# MPPT-BCR.net
KiCad netlist of a schematic drawn in Altium Designer
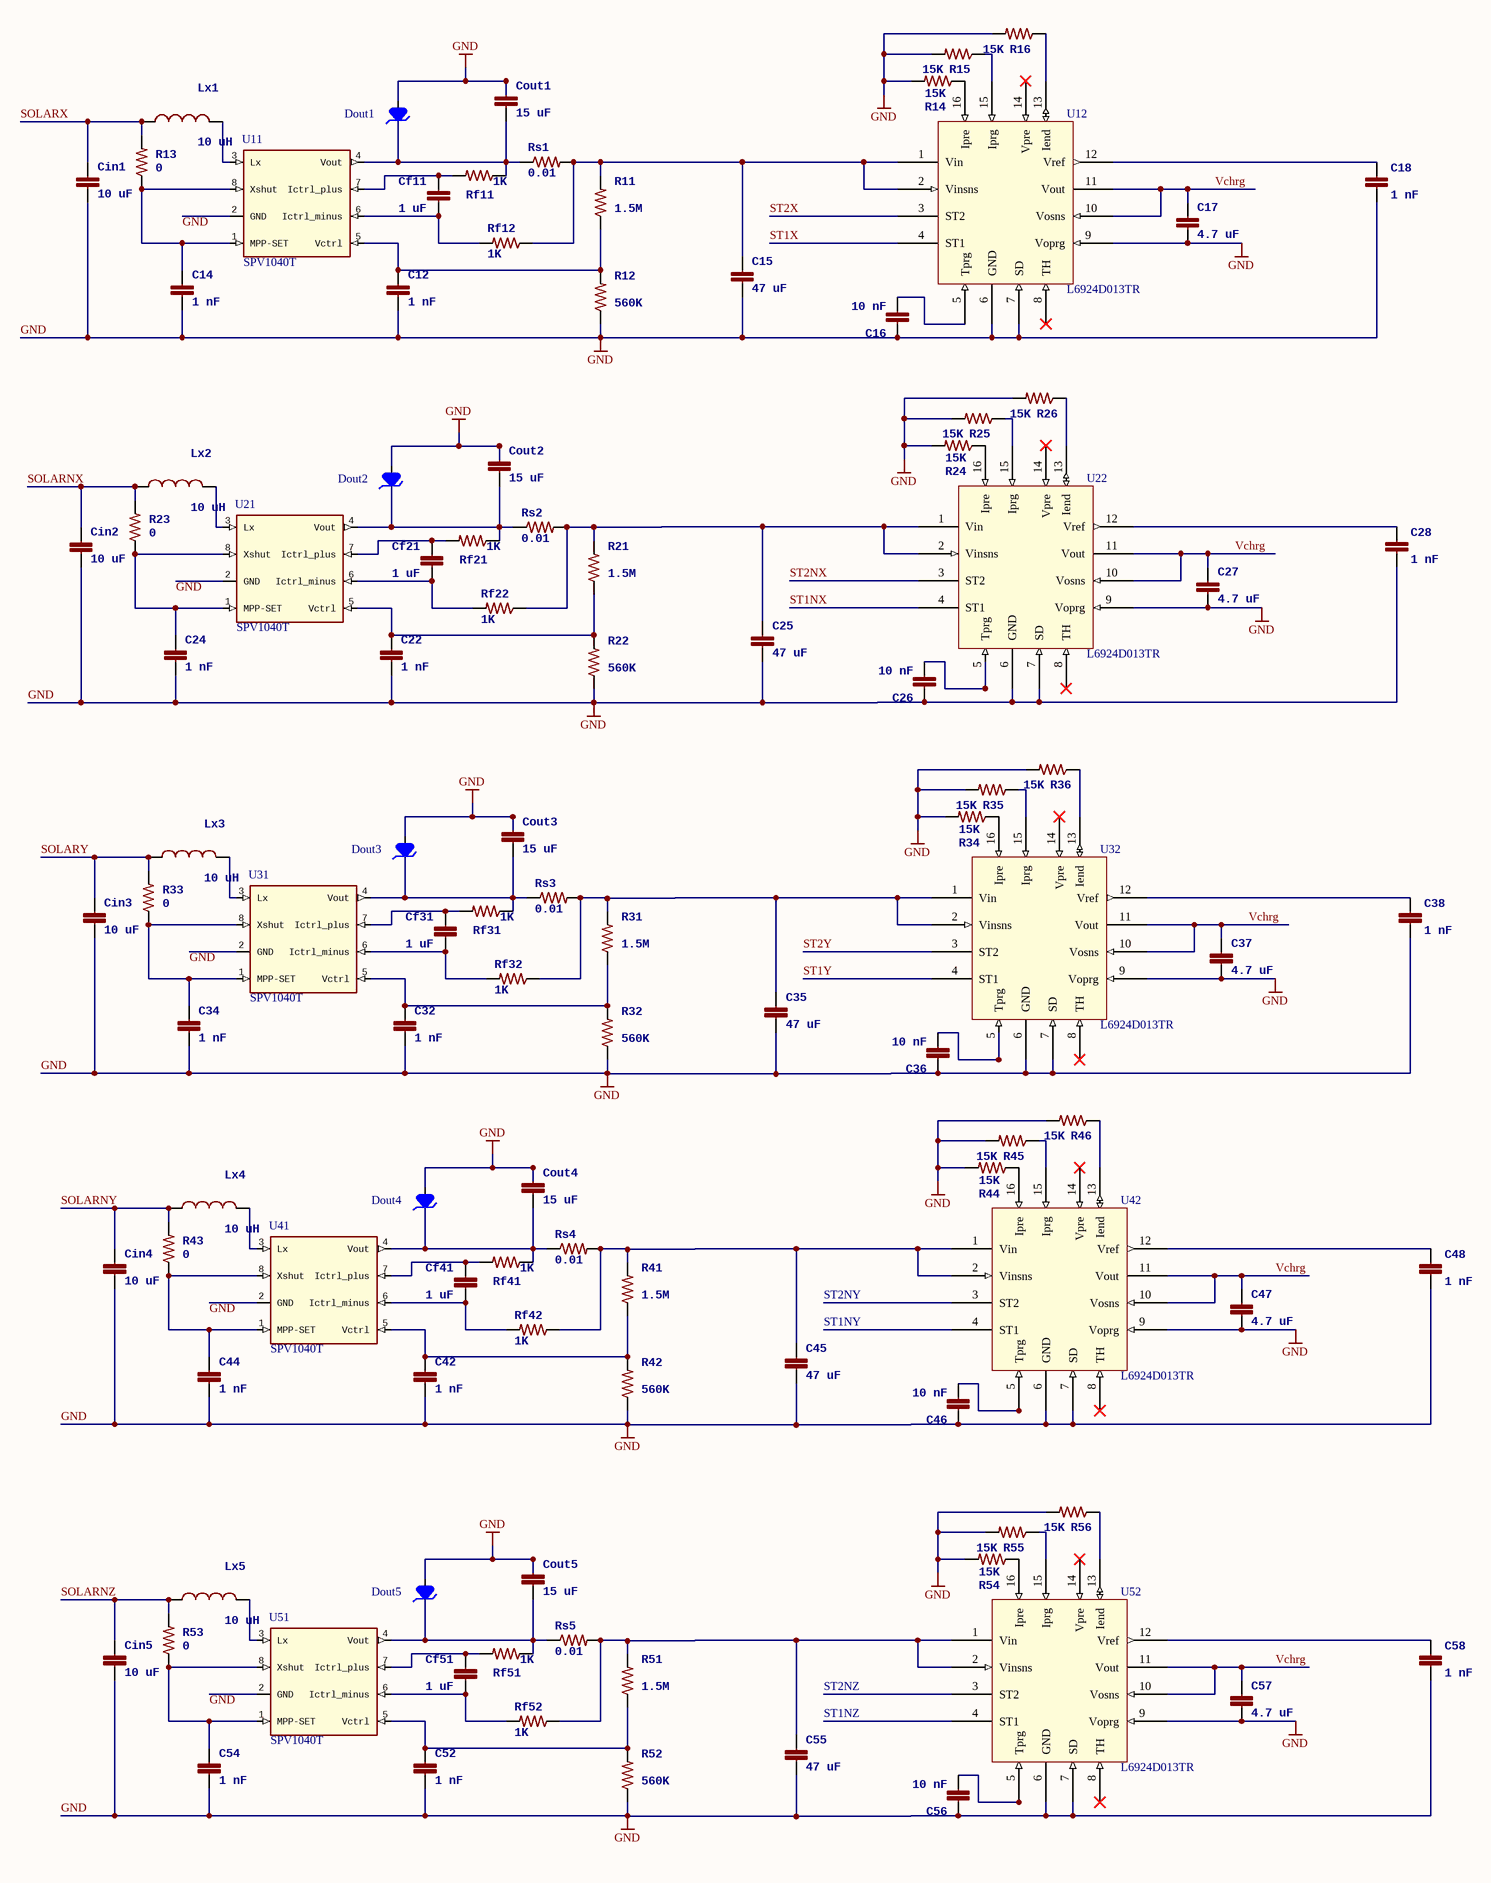
[diagram p0: MPPT-BCR.SchDoc]

(export (version "E")
  (design (tool "Eeschema 10.0.6"))
  (components
    (comp (ref "C12")
      (value "1 nF")
      (footprint "0805")
      (fields (field (name "TOLERANCE") "±10%"))
      (libsource (lib "yusend_power") (part "CAP0805_1nF"))
    )
    (comp (ref "C14")
      (value "1 nF")
      (footprint "0805")
      (fields (field (name "TOLERANCE") "±10%"))
      (libsource (lib "yusend_power") (part "CAP0805_1nF"))
    )
    (comp (ref "C15")
      (value "47 uF")
      (footprint "0805")
      (fields (field (name "TOLERANCE") "±10%"))
      (libsource (lib "yusend_power") (part "CAP0805_47000nF"))
    )
    (comp (ref "C16")
      (value "10 nF")
      (footprint "0805")
      (fields (field (name "TOLERANCE") "±10%"))
      (libsource (lib "yusend_power") (part "CAP0805_10nF"))
    )
    (comp (ref "C17")
      (value "4.7 uF")
      (footprint "0805")
      (fields (field (name "TOLERANCE") "±10%"))
      (libsource (lib "yusend_power") (part "CAP0805_4700nF"))
    )
    (comp (ref "C18")
      (value "1 nF")
      (footprint "0805")
      (fields (field (name "TOLERANCE") "±10%"))
      (libsource (lib "yusend_power") (part "CAP0805_1nF"))
    )
    (comp (ref "C22")
      (value "1 nF")
      (footprint "0805")
      (fields (field (name "TOLERANCE") "±10%"))
      (libsource (lib "yusend_power") (part "CAP0805_1nF"))
    )
    (comp (ref "C24")
      (value "1 nF")
      (footprint "0805")
      (fields (field (name "TOLERANCE") "±10%"))
      (libsource (lib "yusend_power") (part "CAP0805_1nF"))
    )
    (comp (ref "C25")
      (value "47 uF")
      (footprint "0805")
      (fields (field (name "TOLERANCE") "±10%"))
      (libsource (lib "yusend_power") (part "CAP0805_47000nF"))
    )
    (comp (ref "C26")
      (value "10 nF")
      (footprint "0805")
      (fields (field (name "TOLERANCE") "±10%"))
      (libsource (lib "yusend_power") (part "CAP0805_10nF"))
    )
    (comp (ref "C27")
      (value "4.7 uF")
      (footprint "0805")
      (fields (field (name "TOLERANCE") "±10%"))
      (libsource (lib "yusend_power") (part "CAP0805_4700nF"))
    )
    (comp (ref "C28")
      (value "1 nF")
      (footprint "0805")
      (fields (field (name "TOLERANCE") "±10%"))
      (libsource (lib "yusend_power") (part "CAP0805_1nF"))
    )
    (comp (ref "C32")
      (value "1 nF")
      (footprint "0805")
      (fields (field (name "TOLERANCE") "±10%"))
      (libsource (lib "yusend_power") (part "CAP0805_1nF"))
    )
    (comp (ref "C34")
      (value "1 nF")
      (footprint "0805")
      (fields (field (name "TOLERANCE") "±10%"))
      (libsource (lib "yusend_power") (part "CAP0805_1nF"))
    )
    (comp (ref "C35")
      (value "47 uF")
      (footprint "0805")
      (fields (field (name "TOLERANCE") "±10%"))
      (libsource (lib "yusend_power") (part "CAP0805_47000nF"))
    )
    (comp (ref "C36")
      (value "10 nF")
      (footprint "0805")
      (fields (field (name "TOLERANCE") "±10%"))
      (libsource (lib "yusend_power") (part "CAP0805_10nF"))
    )
    (comp (ref "C37")
      (value "4.7 uF")
      (footprint "0805")
      (fields (field (name "TOLERANCE") "±10%"))
      (libsource (lib "yusend_power") (part "CAP0805_4700nF"))
    )
    (comp (ref "C38")
      (value "1 nF")
      (footprint "0805")
      (fields (field (name "TOLERANCE") "±10%"))
      (libsource (lib "yusend_power") (part "CAP0805_1nF"))
    )
    (comp (ref "C42")
      (value "1 nF")
      (footprint "0805")
      (fields (field (name "TOLERANCE") "±10%"))
      (libsource (lib "yusend_power") (part "CAP0805_1nF"))
    )
    (comp (ref "C44")
      (value "1 nF")
      (footprint "0805")
      (fields (field (name "TOLERANCE") "±10%"))
      (libsource (lib "yusend_power") (part "CAP0805_1nF"))
    )
    (comp (ref "C45")
      (value "47 uF")
      (footprint "0805")
      (fields (field (name "TOLERANCE") "±10%"))
      (libsource (lib "yusend_power") (part "CAP0805_47000nF"))
    )
    (comp (ref "C46")
      (value "10 nF")
      (footprint "0805")
      (fields (field (name "TOLERANCE") "±10%"))
      (libsource (lib "yusend_power") (part "CAP0805_10nF"))
    )
    (comp (ref "C47")
      (value "4.7 uF")
      (footprint "0805")
      (fields (field (name "TOLERANCE") "±10%"))
      (libsource (lib "yusend_power") (part "CAP0805_4700nF"))
    )
    (comp (ref "C48")
      (value "1 nF")
      (footprint "0805")
      (fields (field (name "TOLERANCE") "±10%"))
      (libsource (lib "yusend_power") (part "CAP0805_1nF"))
    )
    (comp (ref "C52")
      (value "1 nF")
      (footprint "0805")
      (fields (field (name "TOLERANCE") "±10%"))
      (libsource (lib "yusend_power") (part "CAP0805_1nF"))
    )
    (comp (ref "C54")
      (value "1 nF")
      (footprint "0805")
      (fields (field (name "TOLERANCE") "±10%"))
      (libsource (lib "yusend_power") (part "CAP0805_1nF"))
    )
    (comp (ref "C55")
      (value "47 uF")
      (footprint "0805")
      (fields (field (name "TOLERANCE") "±10%"))
      (libsource (lib "yusend_power") (part "CAP0805_47000nF"))
    )
    (comp (ref "C56")
      (value "10 nF")
      (footprint "0805")
      (fields (field (name "TOLERANCE") "±10%"))
      (libsource (lib "yusend_power") (part "CAP0805_10nF"))
    )
    (comp (ref "C57")
      (value "4.7 uF")
      (footprint "0805")
      (fields (field (name "TOLERANCE") "±10%"))
      (libsource (lib "yusend_power") (part "CAP0805_4700nF"))
    )
    (comp (ref "C58")
      (value "1 nF")
      (footprint "0805")
      (fields (field (name "TOLERANCE") "±10%"))
      (libsource (lib "yusend_power") (part "CAP0805_1nF"))
    )
    (comp (ref "Cf11")
      (value "1 uF")
      (footprint "0805")
      (fields
        (field (name "MANUFACTURER") "Kemet")
        (field (name "MANUFACTURER PART NUMBER") "C0805C105K8RACTU")
        (field (name "TOLERANCE") "±10%")
      )
      (libsource (lib "yusend_power") (part "CAP0805_1uF"))
    )
    (comp (ref "Cf21")
      (value "1 uF")
      (footprint "0805")
      (fields
        (field (name "MANUFACTURER") "Kemet")
        (field (name "MANUFACTURER PART NUMBER") "C0805C105K8RACTU")
        (field (name "TOLERANCE") "±10%")
      )
      (libsource (lib "yusend_power") (part "CAP0805_1uF"))
    )
    (comp (ref "Cf31")
      (value "1 uF")
      (footprint "0805")
      (fields
        (field (name "MANUFACTURER") "Kemet")
        (field (name "MANUFACTURER PART NUMBER") "C0805C105K8RACTU")
        (field (name "TOLERANCE") "±10%")
      )
      (libsource (lib "yusend_power") (part "CAP0805_1uF"))
    )
    (comp (ref "Cf41")
      (value "1 uF")
      (footprint "0805")
      (fields
        (field (name "MANUFACTURER") "Kemet")
        (field (name "MANUFACTURER PART NUMBER") "C0805C105K8RACTU")
        (field (name "TOLERANCE") "±10%")
      )
      (libsource (lib "yusend_power") (part "CAP0805_1uF"))
    )
    (comp (ref "Cf51")
      (value "1 uF")
      (footprint "0805")
      (fields
        (field (name "MANUFACTURER") "Kemet")
        (field (name "MANUFACTURER PART NUMBER") "C0805C105K8RACTU")
        (field (name "TOLERANCE") "±10%")
      )
      (libsource (lib "yusend_power") (part "CAP0805_1uF"))
    )
    (comp (ref "Cin1")
      (value "10 uF")
      (footprint "0805")
      (fields (field (name "TOLERANCE") "±10%"))
      (libsource (lib "yusend_power") (part "CAP0805_10uF"))
    )
    (comp (ref "Cin2")
      (value "10 uF")
      (footprint "0805")
      (fields (field (name "TOLERANCE") "±10%"))
      (libsource (lib "yusend_power") (part "CAP0805_10uF"))
    )
    (comp (ref "Cin3")
      (value "10 uF")
      (footprint "0805")
      (fields (field (name "TOLERANCE") "±10%"))
      (libsource (lib "yusend_power") (part "CAP0805_10uF"))
    )
    (comp (ref "Cin4")
      (value "10 uF")
      (footprint "0805")
      (fields (field (name "TOLERANCE") "±10%"))
      (libsource (lib "yusend_power") (part "CAP0805_10uF"))
    )
    (comp (ref "Cin5")
      (value "10 uF")
      (footprint "0805")
      (fields (field (name "TOLERANCE") "±10%"))
      (libsource (lib "yusend_power") (part "CAP0805_10uF"))
    )
    (comp (ref "Cout1")
      (value "15 uF")
      (footprint "1210")
      (fields (field (name "TOLERANCE") "±10%"))
      (libsource (lib "yusend_power") (part "CAP0805_15uF"))
    )
    (comp (ref "Cout2")
      (value "15 uF")
      (footprint "1210")
      (fields (field (name "TOLERANCE") "±10%"))
      (libsource (lib "yusend_power") (part "CAP0805_15uF"))
    )
    (comp (ref "Cout3")
      (value "15 uF")
      (footprint "1210")
      (fields (field (name "TOLERANCE") "±10%"))
      (libsource (lib "yusend_power") (part "CAP0805_15uF"))
    )
    (comp (ref "Cout4")
      (value "15 uF")
      (footprint "1210")
      (fields (field (name "TOLERANCE") "±10%"))
      (libsource (lib "yusend_power") (part "CAP0805_15uF"))
    )
    (comp (ref "Cout5")
      (value "15 uF")
      (footprint "1210")
      (fields (field (name "TOLERANCE") "±10%"))
      (libsource (lib "yusend_power") (part "CAP0805_15uF"))
    )
    (comp (ref "Dout1")
      (value "Diode_Zener")
      (footprint "STmite")
      (fields (field (name "TOLERANCE") "±5%"))
      (libsource (lib "yusend_power") (part "Diode_Zener"))
    )
    (comp (ref "Dout2")
      (value "Diode_Zener")
      (footprint "STmite")
      (fields (field (name "TOLERANCE") "±5%"))
      (libsource (lib "") (part "Diode_Zener_1"))
    )
    (comp (ref "Dout3")
      (value "Diode_Zener")
      (footprint "STmite")
      (fields (field (name "TOLERANCE") "±5%"))
      (libsource (lib "yusend_power") (part "Diode_Zener"))
    )
    (comp (ref "Dout4")
      (value "Diode_Zener")
      (footprint "STmite")
      (fields (field (name "TOLERANCE") "±5%"))
      (libsource (lib "yusend_power") (part "Diode_Zener"))
    )
    (comp (ref "Dout5")
      (value "Diode_Zener")
      (footprint "STmite")
      (fields (field (name "TOLERANCE") "±5%"))
      (libsource (lib "yusend_power") (part "Diode_Zener"))
    )
    (comp (ref "Lx1")
      (value "10 uH")
      (footprint "1007")
      (libsource (lib "yusend_power") (part "INDUCTOR1007"))
    )
    (comp (ref "Lx2")
      (value "10 uH")
      (footprint "1007")
      (libsource (lib "yusend_power") (part "INDUCTOR1007"))
    )
    (comp (ref "Lx3")
      (value "10 uH")
      (footprint "1007")
      (libsource (lib "yusend_power") (part "INDUCTOR1007"))
    )
    (comp (ref "Lx4")
      (value "10 uH")
      (footprint "1007")
      (libsource (lib "yusend_power") (part "INDUCTOR1007"))
    )
    (comp (ref "Lx5")
      (value "10 uH")
      (footprint "1007")
      (libsource (lib "yusend_power") (part "INDUCTOR1007"))
    )
    (comp (ref "R11")
      (value "1.5M")
      (footprint "0805")
      (fields
        (field (name "MANUFACTURER") "TE Connectivity")
        (field (name "MANUFACTURER PART NUMBER") "1625856-2")
        (field (name "TOLERANCE") "±10%")
      )
      (libsource (lib "yusend_power") (part "RES_0805_1500K"))
    )
    (comp (ref "R12")
      (value "560K")
      (footprint "0805")
      (fields
        (field (name "MANUFACTURER") "TE Connectivity")
        (field (name "MANUFACTURER PART NUMBER") "1625856-2")
        (field (name "TOLERANCE") "±10%")
      )
      (libsource (lib "yusend_power") (part "RES_0805_560K"))
    )
    (comp (ref "R13")
      (value "0")
      (footprint "0805")
      (fields
        (field (name "MANUFACTURER") "TE Connectivity")
        (field (name "MANUFACTURER PART NUMBER") "1625856-2")
        (field (name "TOLERANCE") "±10%")
      )
      (libsource (lib "yusend_power") (part "RES_0805_0"))
    )
    (comp (ref "R14")
      (value "15K")
      (footprint "0805")
      (fields
        (field (name "MANUFACTURER") "TE Connectivity")
        (field (name "MANUFACTURER PART NUMBER") "1625856-2")
        (field (name "TOLERANCE") "±10%")
      )
      (libsource (lib "yusend_power") (part "RES_0805_15K"))
    )
    (comp (ref "R15")
      (value "15K")
      (footprint "0805")
      (fields
        (field (name "MANUFACTURER") "TE Connectivity")
        (field (name "MANUFACTURER PART NUMBER") "1625856-2")
        (field (name "TOLERANCE") "±10%")
      )
      (libsource (lib "yusend_power") (part "RES_0805_15K"))
    )
    (comp (ref "R16")
      (value "15K")
      (footprint "0805")
      (fields
        (field (name "MANUFACTURER") "TE Connectivity")
        (field (name "MANUFACTURER PART NUMBER") "1625856-2")
        (field (name "TOLERANCE") "±10%")
      )
      (libsource (lib "yusend_power") (part "RES_0805_15K"))
    )
    (comp (ref "R21")
      (value "1.5M")
      (footprint "0805")
      (fields
        (field (name "MANUFACTURER") "TE Connectivity")
        (field (name "MANUFACTURER PART NUMBER") "1625856-2")
        (field (name "TOLERANCE") "±10%")
      )
      (libsource (lib "yusend_power") (part "RES_0805_1500K"))
    )
    (comp (ref "R22")
      (value "560K")
      (footprint "0805")
      (fields
        (field (name "MANUFACTURER") "TE Connectivity")
        (field (name "MANUFACTURER PART NUMBER") "1625856-2")
        (field (name "TOLERANCE") "±10%")
      )
      (libsource (lib "yusend_power") (part "RES_0805_560K"))
    )
    (comp (ref "R23")
      (value "0")
      (footprint "0805")
      (fields
        (field (name "MANUFACTURER") "TE Connectivity")
        (field (name "MANUFACTURER PART NUMBER") "1625856-2")
        (field (name "TOLERANCE") "±10%")
      )
      (libsource (lib "yusend_power") (part "RES_0805_0"))
    )
    (comp (ref "R24")
      (value "15K")
      (footprint "0805")
      (fields
        (field (name "MANUFACTURER") "TE Connectivity")
        (field (name "MANUFACTURER PART NUMBER") "1625856-2")
        (field (name "TOLERANCE") "±10%")
      )
      (libsource (lib "yusend_power") (part "RES_0805_15K"))
    )
    (comp (ref "R25")
      (value "15K")
      (footprint "0805")
      (fields
        (field (name "MANUFACTURER") "TE Connectivity")
        (field (name "MANUFACTURER PART NUMBER") "1625856-2")
        (field (name "TOLERANCE") "±10%")
      )
      (libsource (lib "yusend_power") (part "RES_0805_15K"))
    )
    (comp (ref "R26")
      (value "15K")
      (footprint "0805")
      (fields
        (field (name "MANUFACTURER") "TE Connectivity")
        (field (name "MANUFACTURER PART NUMBER") "1625856-2")
        (field (name "TOLERANCE") "±10%")
      )
      (libsource (lib "yusend_power") (part "RES_0805_15K"))
    )
    (comp (ref "R31")
      (value "1.5M")
      (footprint "0805")
      (fields
        (field (name "MANUFACTURER") "TE Connectivity")
        (field (name "MANUFACTURER PART NUMBER") "1625856-2")
        (field (name "TOLERANCE") "±10%")
      )
      (libsource (lib "yusend_power") (part "RES_0805_1500K"))
    )
    (comp (ref "R32")
      (value "560K")
      (footprint "0805")
      (fields
        (field (name "MANUFACTURER") "TE Connectivity")
        (field (name "MANUFACTURER PART NUMBER") "1625856-2")
        (field (name "TOLERANCE") "±10%")
      )
      (libsource (lib "yusend_power") (part "RES_0805_560K"))
    )
    (comp (ref "R33")
      (value "0")
      (footprint "0805")
      (fields
        (field (name "MANUFACTURER") "TE Connectivity")
        (field (name "MANUFACTURER PART NUMBER") "1625856-2")
        (field (name "TOLERANCE") "±10%")
      )
      (libsource (lib "yusend_power") (part "RES_0805_0"))
    )
    (comp (ref "R34")
      (value "15K")
      (footprint "0805")
      (fields
        (field (name "MANUFACTURER") "TE Connectivity")
        (field (name "MANUFACTURER PART NUMBER") "1625856-2")
        (field (name "TOLERANCE") "±10%")
      )
      (libsource (lib "yusend_power") (part "RES_0805_15K"))
    )
    (comp (ref "R35")
      (value "15K")
      (footprint "0805")
      (fields
        (field (name "MANUFACTURER") "TE Connectivity")
        (field (name "MANUFACTURER PART NUMBER") "1625856-2")
        (field (name "TOLERANCE") "±10%")
      )
      (libsource (lib "yusend_power") (part "RES_0805_15K"))
    )
    (comp (ref "R36")
      (value "15K")
      (footprint "0805")
      (fields
        (field (name "MANUFACTURER") "TE Connectivity")
        (field (name "MANUFACTURER PART NUMBER") "1625856-2")
        (field (name "TOLERANCE") "±10%")
      )
      (libsource (lib "yusend_power") (part "RES_0805_15K"))
    )
    (comp (ref "R41")
      (value "1.5M")
      (footprint "0805")
      (fields
        (field (name "MANUFACTURER") "TE Connectivity")
        (field (name "MANUFACTURER PART NUMBER") "1625856-2")
        (field (name "TOLERANCE") "±10%")
      )
      (libsource (lib "yusend_power") (part "RES_0805_1500K"))
    )
    (comp (ref "R42")
      (value "560K")
      (footprint "0805")
      (fields
        (field (name "MANUFACTURER") "TE Connectivity")
        (field (name "MANUFACTURER PART NUMBER") "1625856-2")
        (field (name "TOLERANCE") "±10%")
      )
      (libsource (lib "yusend_power") (part "RES_0805_560K"))
    )
    (comp (ref "R43")
      (value "0")
      (footprint "0805")
      (fields
        (field (name "MANUFACTURER") "TE Connectivity")
        (field (name "MANUFACTURER PART NUMBER") "1625856-2")
        (field (name "TOLERANCE") "±10%")
      )
      (libsource (lib "yusend_power") (part "RES_0805_0"))
    )
    (comp (ref "R44")
      (value "15K")
      (footprint "0805")
      (fields
        (field (name "MANUFACTURER") "TE Connectivity")
        (field (name "MANUFACTURER PART NUMBER") "1625856-2")
        (field (name "TOLERANCE") "±10%")
      )
      (libsource (lib "yusend_power") (part "RES_0805_15K"))
    )
    (comp (ref "R45")
      (value "15K")
      (footprint "0805")
      (fields
        (field (name "MANUFACTURER") "TE Connectivity")
        (field (name "MANUFACTURER PART NUMBER") "1625856-2")
        (field (name "TOLERANCE") "±10%")
      )
      (libsource (lib "yusend_power") (part "RES_0805_15K"))
    )
    (comp (ref "R46")
      (value "15K")
      (footprint "0805")
      (fields
        (field (name "MANUFACTURER") "TE Connectivity")
        (field (name "MANUFACTURER PART NUMBER") "1625856-2")
        (field (name "TOLERANCE") "±10%")
      )
      (libsource (lib "yusend_power") (part "RES_0805_15K"))
    )
    (comp (ref "R51")
      (value "1.5M")
      (footprint "0805")
      (fields
        (field (name "MANUFACTURER") "TE Connectivity")
        (field (name "MANUFACTURER PART NUMBER") "1625856-2")
        (field (name "TOLERANCE") "±10%")
      )
      (libsource (lib "yusend_power") (part "RES_0805_1500K"))
    )
    (comp (ref "R52")
      (value "560K")
      (footprint "0805")
      (fields
        (field (name "MANUFACTURER") "TE Connectivity")
        (field (name "MANUFACTURER PART NUMBER") "1625856-2")
        (field (name "TOLERANCE") "±10%")
      )
      (libsource (lib "yusend_power") (part "RES_0805_560K"))
    )
    (comp (ref "R53")
      (value "0")
      (footprint "0805")
      (fields
        (field (name "MANUFACTURER") "TE Connectivity")
        (field (name "MANUFACTURER PART NUMBER") "1625856-2")
        (field (name "TOLERANCE") "±10%")
      )
      (libsource (lib "yusend_power") (part "RES_0805_0"))
    )
    (comp (ref "R54")
      (value "15K")
      (footprint "0805")
      (fields
        (field (name "MANUFACTURER") "TE Connectivity")
        (field (name "MANUFACTURER PART NUMBER") "1625856-2")
        (field (name "TOLERANCE") "±10%")
      )
      (libsource (lib "yusend_power") (part "RES_0805_15K"))
    )
    (comp (ref "R55")
      (value "15K")
      (footprint "0805")
      (fields
        (field (name "MANUFACTURER") "TE Connectivity")
        (field (name "MANUFACTURER PART NUMBER") "1625856-2")
        (field (name "TOLERANCE") "±10%")
      )
      (libsource (lib "yusend_power") (part "RES_0805_15K"))
    )
    (comp (ref "R56")
      (value "15K")
      (footprint "0805")
      (fields
        (field (name "MANUFACTURER") "TE Connectivity")
        (field (name "MANUFACTURER PART NUMBER") "1625856-2")
        (field (name "TOLERANCE") "±10%")
      )
      (libsource (lib "yusend_power") (part "RES_0805_15K"))
    )
    (comp (ref "Rf11")
      (value "1K")
      (footprint "0805")
      (fields
        (field (name "MANUFACTURER") "TE Connectivity")
        (field (name "MANUFACTURER PART NUMBER") "1625856-2")
        (field (name "TOLERANCE") "±10%")
      )
      (libsource (lib "yusend_power") (part "RES_0805_1K"))
    )
    (comp (ref "Rf12")
      (value "1K")
      (footprint "0805")
      (fields
        (field (name "MANUFACTURER") "TE Connectivity")
        (field (name "MANUFACTURER PART NUMBER") "1625856-2")
        (field (name "TOLERANCE") "±10%")
      )
      (libsource (lib "yusend_power") (part "RES_0805_1K"))
    )
    (comp (ref "Rf21")
      (value "1K")
      (footprint "0805")
      (fields
        (field (name "MANUFACTURER") "TE Connectivity")
        (field (name "MANUFACTURER PART NUMBER") "1625856-2")
        (field (name "TOLERANCE") "±10%")
      )
      (libsource (lib "yusend_power") (part "RES_0805_1K"))
    )
    (comp (ref "Rf22")
      (value "1K")
      (footprint "0805")
      (fields
        (field (name "MANUFACTURER") "TE Connectivity")
        (field (name "MANUFACTURER PART NUMBER") "1625856-2")
        (field (name "TOLERANCE") "±10%")
      )
      (libsource (lib "yusend_power") (part "RES_0805_1K"))
    )
    (comp (ref "Rf31")
      (value "1K")
      (footprint "0805")
      (fields
        (field (name "MANUFACTURER") "TE Connectivity")
        (field (name "MANUFACTURER PART NUMBER") "1625856-2")
        (field (name "TOLERANCE") "±10%")
      )
      (libsource (lib "yusend_power") (part "RES_0805_1K"))
    )
    (comp (ref "Rf32")
      (value "1K")
      (footprint "0805")
      (fields
        (field (name "MANUFACTURER") "TE Connectivity")
        (field (name "MANUFACTURER PART NUMBER") "1625856-2")
        (field (name "TOLERANCE") "±10%")
      )
      (libsource (lib "yusend_power") (part "RES_0805_1K"))
    )
    (comp (ref "Rf41")
      (value "1K")
      (footprint "0805")
      (fields
        (field (name "MANUFACTURER") "TE Connectivity")
        (field (name "MANUFACTURER PART NUMBER") "1625856-2")
        (field (name "TOLERANCE") "±10%")
      )
      (libsource (lib "yusend_power") (part "RES_0805_1K"))
    )
    (comp (ref "Rf42")
      (value "1K")
      (footprint "0805")
      (fields
        (field (name "MANUFACTURER") "TE Connectivity")
        (field (name "MANUFACTURER PART NUMBER") "1625856-2")
        (field (name "TOLERANCE") "±10%")
      )
      (libsource (lib "yusend_power") (part "RES_0805_1K"))
    )
    (comp (ref "Rf51")
      (value "1K")
      (footprint "0805")
      (fields
        (field (name "MANUFACTURER") "TE Connectivity")
        (field (name "MANUFACTURER PART NUMBER") "1625856-2")
        (field (name "TOLERANCE") "±10%")
      )
      (libsource (lib "yusend_power") (part "RES_0805_1K"))
    )
    (comp (ref "Rf52")
      (value "1K")
      (footprint "0805")
      (fields
        (field (name "MANUFACTURER") "TE Connectivity")
        (field (name "MANUFACTURER PART NUMBER") "1625856-2")
        (field (name "TOLERANCE") "±10%")
      )
      (libsource (lib "yusend_power") (part "RES_0805_1K"))
    )
    (comp (ref "Rs1")
      (value "0.01")
      (footprint "0805")
      (fields
        (field (name "MANUFACTURER") "TE Connectivity")
        (field (name "MANUFACTURER PART NUMBER") "1625856-2")
        (field (name "TOLERANCE") "±10%")
      )
      (libsource (lib "yusend_power") (part "RES_0805_01"))
    )
    (comp (ref "Rs2")
      (value "0.01")
      (footprint "0805")
      (fields
        (field (name "MANUFACTURER") "TE Connectivity")
        (field (name "MANUFACTURER PART NUMBER") "1625856-2")
        (field (name "TOLERANCE") "±10%")
      )
      (libsource (lib "yusend_power") (part "RES_0805_01"))
    )
    (comp (ref "Rs3")
      (value "0.01")
      (footprint "0805")
      (fields
        (field (name "MANUFACTURER") "TE Connectivity")
        (field (name "MANUFACTURER PART NUMBER") "1625856-2")
        (field (name "TOLERANCE") "±10%")
      )
      (libsource (lib "yusend_power") (part "RES_0805_01"))
    )
    (comp (ref "Rs4")
      (value "0.01")
      (footprint "0805")
      (fields
        (field (name "MANUFACTURER") "TE Connectivity")
        (field (name "MANUFACTURER PART NUMBER") "1625856-2")
        (field (name "TOLERANCE") "±10%")
      )
      (libsource (lib "yusend_power") (part "RES_0805_01"))
    )
    (comp (ref "Rs5")
      (value "0.01")
      (footprint "0805")
      (fields
        (field (name "MANUFACTURER") "TE Connectivity")
        (field (name "MANUFACTURER PART NUMBER") "1625856-2")
        (field (name "TOLERANCE") "±10%")
      )
      (libsource (lib "yusend_power") (part "RES_0805_01"))
    )
    (comp (ref "U11")
      (value "SPV1040")
      (footprint "TSSOP8")
      (fields
        (field (name "MANUFACTURER") "STMicroelectronics")
        (field (name "MANUFACTURER PART NUMBER") "SPV1040T")
      )
      (libsource (lib "yusend_power") (part "SPV1040"))
    )
    (comp (ref "U12")
      (value "L6924D013TR")
      (footprint "VQFN16_AP")
      (description "IC BATT CHRGR ION/POLY 16-VFQFPN")
      (fields (field (name "MANUFACTURER") "STMicroelectronics"))
      (libsource (lib "yusend_power") (part "L6924D013TR"))
    )
    (comp (ref "U21")
      (value "SPV1040")
      (footprint "TSSOP8")
      (fields
        (field (name "MANUFACTURER") "STMicroelectronics")
        (field (name "MANUFACTURER PART NUMBER") "SPV1040T")
      )
      (libsource (lib "") (part "SPV1040_1"))
    )
    (comp (ref "U22")
      (value "L6924D013TR")
      (footprint "VQFN16_AP")
      (description "IC BATT CHRGR ION/POLY 16-VFQFPN")
      (fields (field (name "MANUFACTURER") "STMicroelectronics"))
      (libsource (lib "yusend_power") (part "L6924D013TR"))
    )
    (comp (ref "U31")
      (value "SPV1040")
      (footprint "TSSOP8")
      (fields
        (field (name "MANUFACTURER") "STMicroelectronics")
        (field (name "MANUFACTURER PART NUMBER") "SPV1040T")
      )
      (libsource (lib "yusend_power") (part "SPV1040"))
    )
    (comp (ref "U32")
      (value "L6924D013TR")
      (footprint "VQFN16_AP")
      (description "IC BATT CHRGR ION/POLY 16-VFQFPN")
      (fields (field (name "MANUFACTURER") "STMicroelectronics"))
      (libsource (lib "yusend_power") (part "L6924D013TR"))
    )
    (comp (ref "U41")
      (value "SPV1040")
      (footprint "TSSOP8")
      (fields
        (field (name "MANUFACTURER") "STMicroelectronics")
        (field (name "MANUFACTURER PART NUMBER") "SPV1040T")
      )
      (libsource (lib "yusend_power") (part "SPV1040"))
    )
    (comp (ref "U42")
      (value "L6924D013TR")
      (footprint "VQFN16_AP")
      (description "IC BATT CHRGR ION/POLY 16-VFQFPN")
      (fields (field (name "MANUFACTURER") "STMicroelectronics"))
      (libsource (lib "yusend_power") (part "L6924D013TR"))
    )
    (comp (ref "U51")
      (value "SPV1040")
      (footprint "TSSOP8")
      (fields
        (field (name "MANUFACTURER") "STMicroelectronics")
        (field (name "MANUFACTURER PART NUMBER") "SPV1040T")
      )
      (libsource (lib "yusend_power") (part "SPV1040"))
    )
    (comp (ref "U52")
      (value "L6924D013TR")
      (footprint "VQFN16_AP")
      (description "IC BATT CHRGR ION/POLY 16-VFQFPN")
      (fields (field (name "MANUFACTURER") "STMicroelectronics"))
      (libsource (lib "yusend_power") (part "L6924D013TR"))
    )
  )
  (nets
    (net (code "1") (name "/SOLARNX") (class "Default")
      (node (ref "Cin2") (pin "1") (pinfunction "1_1") (pintype "passive"))
      (node (ref "Lx2") (pin "1") (pinfunction "1_1") (pintype "passive"))
      (node (ref "R23") (pin "2") (pinfunction "2_2") (pintype "passive"))
    )
    (net (code "2") (name "/SOLARNY") (class "Default")
      (node (ref "Cin4") (pin "1") (pinfunction "1_1") (pintype "passive"))
      (node (ref "Lx4") (pin "1") (pinfunction "1_1") (pintype "passive"))
      (node (ref "R43") (pin "2") (pinfunction "2_2") (pintype "passive"))
    )
    (net (code "3") (name "/SOLARNZ") (class "Default")
      (node (ref "Cin5") (pin "1") (pinfunction "1_1") (pintype "passive"))
      (node (ref "Lx5") (pin "1") (pinfunction "1_1") (pintype "passive"))
      (node (ref "R53") (pin "2") (pinfunction "2_2") (pintype "passive"))
    )
    (net (code "4") (name "/SOLARX") (class "Default")
      (node (ref "Cin1") (pin "1") (pinfunction "1_1") (pintype "passive"))
      (node (ref "Lx1") (pin "1") (pinfunction "1_1") (pintype "passive"))
      (node (ref "R13") (pin "2") (pinfunction "2_2") (pintype "passive"))
    )
    (net (code "5") (name "/SOLARY") (class "Default")
      (node (ref "Cin3") (pin "1") (pinfunction "1_1") (pintype "passive"))
      (node (ref "Lx3") (pin "1") (pinfunction "1_1") (pintype "passive"))
      (node (ref "R33") (pin "2") (pinfunction "2_2") (pintype "passive"))
    )
    (net (code "6") (name "/ST1NX") (class "Default")
      (node (ref "U22") (pin "4") (pinfunction "ST1_4") (pintype "open_collector"))
    )
    (net (code "7") (name "/ST1X") (class "Default")
      (node (ref "U12") (pin "4") (pinfunction "ST1_4") (pintype "open_collector"))
    )
    (net (code "8") (name "/ST1Y") (class "Default")
      (node (ref "U32") (pin "4") (pinfunction "ST1_4") (pintype "open_collector"))
    )
    (net (code "9") (name "/ST2NX") (class "Default")
      (node (ref "U22") (pin "3") (pinfunction "ST2_3") (pintype "open_collector"))
    )
    (net (code "10") (name "/ST2X") (class "Default")
      (node (ref "U12") (pin "3") (pinfunction "ST2_3") (pintype "open_collector"))
    )
    (net (code "11") (name "/ST2Y") (class "Default")
      (node (ref "U32") (pin "3") (pinfunction "ST2_3") (pintype "open_collector"))
    )
    (net (code "12") (name "/Vchrg") (class "Default")
      (node (ref "C17") (pin "1") (pinfunction "1_1") (pintype "passive"))
      (node (ref "C27") (pin "1") (pinfunction "1_1") (pintype "passive"))
      (node (ref "C37") (pin "1") (pinfunction "1_1") (pintype "passive"))
      (node (ref "C47") (pin "1") (pinfunction "1_1") (pintype "passive"))
      (node (ref "C57") (pin "1") (pinfunction "1_1") (pintype "passive"))
      (node (ref "U12") (pin "10") (pinfunction "Vosns_10") (pintype "input"))
      (node (ref "U12") (pin "11") (pinfunction "Vout_11") (pintype "power_in"))
      (node (ref "U22") (pin "10") (pinfunction "Vosns_10") (pintype "input"))
      (node (ref "U22") (pin "11") (pinfunction "Vout_11") (pintype "power_in"))
      (node (ref "U32") (pin "10") (pinfunction "Vosns_10") (pintype "input"))
      (node (ref "U32") (pin "11") (pinfunction "Vout_11") (pintype "power_in"))
      (node (ref "U42") (pin "10") (pinfunction "Vosns_10") (pintype "input"))
      (node (ref "U42") (pin "11") (pinfunction "Vout_11") (pintype "power_in"))
      (node (ref "U52") (pin "10") (pinfunction "Vosns_10") (pintype "input"))
      (node (ref "U52") (pin "11") (pinfunction "Vout_11") (pintype "power_in"))
    )
    (net (code "13") (name "GND") (class "Default")
      (node (ref "C12") (pin "2") (pinfunction "2_2") (pintype "passive"))
      (node (ref "C14") (pin "2") (pinfunction "2_2") (pintype "passive"))
      (node (ref "C15") (pin "2") (pinfunction "2_2") (pintype "passive"))
      (node (ref "C16") (pin "1") (pinfunction "1_1") (pintype "passive"))
      (node (ref "C17") (pin "2") (pinfunction "2_2") (pintype "passive"))
      (node (ref "C18") (pin "2") (pinfunction "2_2") (pintype "passive"))
      (node (ref "C22") (pin "2") (pinfunction "2_2") (pintype "passive"))
      (node (ref "C24") (pin "2") (pinfunction "2_2") (pintype "passive"))
      (node (ref "C25") (pin "2") (pinfunction "2_2") (pintype "passive"))
      (node (ref "C26") (pin "1") (pinfunction "1_1") (pintype "passive"))
      (node (ref "C27") (pin "2") (pinfunction "2_2") (pintype "passive"))
      (node (ref "C28") (pin "2") (pinfunction "2_2") (pintype "passive"))
      (node (ref "C32") (pin "2") (pinfunction "2_2") (pintype "passive"))
      (node (ref "C34") (pin "2") (pinfunction "2_2") (pintype "passive"))
      (node (ref "C35") (pin "2") (pinfunction "2_2") (pintype "passive"))
      (node (ref "C36") (pin "1") (pinfunction "1_1") (pintype "passive"))
      (node (ref "C37") (pin "2") (pinfunction "2_2") (pintype "passive"))
      (node (ref "C38") (pin "2") (pinfunction "2_2") (pintype "passive"))
      (node (ref "C42") (pin "2") (pinfunction "2_2") (pintype "passive"))
      (node (ref "C44") (pin "2") (pinfunction "2_2") (pintype "passive"))
      (node (ref "C45") (pin "2") (pinfunction "2_2") (pintype "passive"))
      (node (ref "C46") (pin "1") (pinfunction "1_1") (pintype "passive"))
      (node (ref "C47") (pin "2") (pinfunction "2_2") (pintype "passive"))
      (node (ref "C48") (pin "2") (pinfunction "2_2") (pintype "passive"))
      (node (ref "C52") (pin "2") (pinfunction "2_2") (pintype "passive"))
      (node (ref "C54") (pin "2") (pinfunction "2_2") (pintype "passive"))
      (node (ref "C55") (pin "2") (pinfunction "2_2") (pintype "passive"))
      (node (ref "C56") (pin "1") (pinfunction "1_1") (pintype "passive"))
      (node (ref "C57") (pin "2") (pinfunction "2_2") (pintype "passive"))
      (node (ref "C58") (pin "2") (pinfunction "2_2") (pintype "passive"))
      (node (ref "Cin1") (pin "2") (pinfunction "2_2") (pintype "passive"))
      (node (ref "Cin2") (pin "2") (pinfunction "2_2") (pintype "passive"))
      (node (ref "Cin3") (pin "2") (pinfunction "2_2") (pintype "passive"))
      (node (ref "Cin4") (pin "2") (pinfunction "2_2") (pintype "passive"))
      (node (ref "Cin5") (pin "2") (pinfunction "2_2") (pintype "passive"))
      (node (ref "Cout1") (pin "1") (pinfunction "1_1") (pintype "passive"))
      (node (ref "Cout2") (pin "1") (pinfunction "1_1") (pintype "passive"))
      (node (ref "Cout3") (pin "1") (pinfunction "1_1") (pintype "passive"))
      (node (ref "Cout4") (pin "1") (pinfunction "1_1") (pintype "passive"))
      (node (ref "Cout5") (pin "1") (pinfunction "1_1") (pintype "passive"))
      (node (ref "Dout1") (pin "2") (pinfunction "2_2") (pintype "passive"))
      (node (ref "Dout2") (pin "2") (pinfunction "2_2") (pintype "passive"))
      (node (ref "Dout3") (pin "2") (pinfunction "2_2") (pintype "passive"))
      (node (ref "Dout4") (pin "2") (pinfunction "2_2") (pintype "passive"))
      (node (ref "Dout5") (pin "2") (pinfunction "2_2") (pintype "passive"))
      (node (ref "R12") (pin "1") (pinfunction "1_1") (pintype "passive"))
      (node (ref "R14") (pin "2") (pinfunction "2_2") (pintype "passive"))
      (node (ref "R15") (pin "2") (pinfunction "2_2") (pintype "passive"))
      (node (ref "R16") (pin "2") (pinfunction "2_2") (pintype "passive"))
      (node (ref "R22") (pin "1") (pinfunction "1_1") (pintype "passive"))
      (node (ref "R24") (pin "2") (pinfunction "2_2") (pintype "passive"))
      (node (ref "R25") (pin "2") (pinfunction "2_2") (pintype "passive"))
      (node (ref "R26") (pin "2") (pinfunction "2_2") (pintype "passive"))
      (node (ref "R32") (pin "1") (pinfunction "1_1") (pintype "passive"))
      (node (ref "R34") (pin "2") (pinfunction "2_2") (pintype "passive"))
      (node (ref "R35") (pin "2") (pinfunction "2_2") (pintype "passive"))
      (node (ref "R36") (pin "2") (pinfunction "2_2") (pintype "passive"))
      (node (ref "R42") (pin "1") (pinfunction "1_1") (pintype "passive"))
      (node (ref "R44") (pin "2") (pinfunction "2_2") (pintype "passive"))
      (node (ref "R45") (pin "2") (pinfunction "2_2") (pintype "passive"))
      (node (ref "R46") (pin "2") (pinfunction "2_2") (pintype "passive"))
      (node (ref "R52") (pin "1") (pinfunction "1_1") (pintype "passive"))
      (node (ref "R54") (pin "2") (pinfunction "2_2") (pintype "passive"))
      (node (ref "R55") (pin "2") (pinfunction "2_2") (pintype "passive"))
      (node (ref "R56") (pin "2") (pinfunction "2_2") (pintype "passive"))
      (node (ref "U12") (pin "6") (pinfunction "GND_6") (pintype "power_in"))
      (node (ref "U12") (pin "7") (pinfunction "SD_7") (pintype "input"))
      (node (ref "U12") (pin "9") (pinfunction "Voprg_9") (pintype "input"))
      (node (ref "U22") (pin "6") (pinfunction "GND_6") (pintype "power_in"))
      (node (ref "U22") (pin "7") (pinfunction "SD_7") (pintype "input"))
      (node (ref "U22") (pin "9") (pinfunction "Voprg_9") (pintype "input"))
      (node (ref "U32") (pin "6") (pinfunction "GND_6") (pintype "power_in"))
      (node (ref "U32") (pin "7") (pinfunction "SD_7") (pintype "input"))
      (node (ref "U32") (pin "9") (pinfunction "Voprg_9") (pintype "input"))
      (node (ref "U42") (pin "6") (pinfunction "GND_6") (pintype "power_in"))
      (node (ref "U42") (pin "7") (pinfunction "SD_7") (pintype "input"))
      (node (ref "U42") (pin "9") (pinfunction "Voprg_9") (pintype "input"))
      (node (ref "U52") (pin "6") (pinfunction "GND_6") (pintype "power_in"))
      (node (ref "U52") (pin "7") (pinfunction "SD_7") (pintype "input"))
      (node (ref "U52") (pin "9") (pinfunction "Voprg_9") (pintype "input"))
    )
    (net (code "14") (name "Net-(U11-Ictrl_minus)") (class "Default")
      (node (ref "Cf11") (pin "2") (pinfunction "2_2") (pintype "passive"))
      (node (ref "Rf12") (pin "2") (pinfunction "2_2") (pintype "passive"))
      (node (ref "U11") (pin "6") (pinfunction "Ictrl_minus_6") (pintype "input"))
    )
    (net (code "15") (name "Net-(U11-Ictrl_plus)") (class "Default")
      (node (ref "Cf11") (pin "1") (pinfunction "1_1") (pintype "passive"))
      (node (ref "Rf11") (pin "2") (pinfunction "2_2") (pintype "passive"))
      (node (ref "U11") (pin "7") (pinfunction "Ictrl_plus_7") (pintype "input"))
    )
    (net (code "16") (name "Net-(U11-Lx)") (class "Default")
      (node (ref "Lx1") (pin "2") (pinfunction "2_2") (pintype "passive"))
      (node (ref "U11") (pin "3") (pinfunction "Lx_3") (pintype "input"))
    )
    (net (code "17") (name "Net-(U11-MPP-SET)") (class "Default")
      (node (ref "C14") (pin "1") (pinfunction "1_1") (pintype "passive"))
      (node (ref "R13") (pin "1") (pinfunction "1_1") (pintype "passive"))
      (node (ref "U11") (pin "1") (pinfunction "MPP-SET_1") (pintype "input"))
      (node (ref "U11") (pin "8") (pinfunction "Xshut_8") (pintype "input"))
    )
    (net (code "18") (name "Net-(U11-Vctrl)") (class "Default")
      (node (ref "C12") (pin "1") (pinfunction "1_1") (pintype "passive"))
      (node (ref "R11") (pin "1") (pinfunction "1_1") (pintype "passive"))
      (node (ref "R12") (pin "2") (pinfunction "2_2") (pintype "passive"))
      (node (ref "U11") (pin "5") (pinfunction "Vctrl_5") (pintype "input"))
    )
    (net (code "19") (name "Net-(U11-Vout)") (class "Default")
      (node (ref "Cout1") (pin "2") (pinfunction "2_2") (pintype "passive"))
      (node (ref "Dout1") (pin "1") (pinfunction "1_1") (pintype "passive"))
      (node (ref "Rf11") (pin "1") (pinfunction "1_1") (pintype "passive"))
      (node (ref "Rs1") (pin "1") (pinfunction "1_1") (pintype "passive"))
      (node (ref "U11") (pin "4") (pinfunction "Vout_4") (pintype "output"))
    )
    (net (code "20") (name "Net-(U12-Iend)") (class "Default")
      (node (ref "R16") (pin "1") (pinfunction "1_1") (pintype "passive"))
      (node (ref "U12") (pin "13") (pinfunction "Iend_13") (pintype "bidirectional"))
    )
    (net (code "21") (name "Net-(U12-Ipre)") (class "Default")
      (node (ref "R14") (pin "1") (pinfunction "1_1") (pintype "passive"))
      (node (ref "U12") (pin "16") (pinfunction "Ipre_16") (pintype "input"))
    )
    (net (code "22") (name "Net-(U12-Iprg)") (class "Default")
      (node (ref "R15") (pin "1") (pinfunction "1_1") (pintype "passive"))
      (node (ref "U12") (pin "15") (pinfunction "Iprg_15") (pintype "input"))
    )
    (net (code "23") (name "Net-(U12-Tprg)") (class "Default")
      (node (ref "C16") (pin "2") (pinfunction "2_2") (pintype "passive"))
      (node (ref "U12") (pin "5") (pinfunction "Tprg_5") (pintype "input"))
    )
    (net (code "24") (name "Net-(U12-Vin)") (class "Default")
      (node (ref "C15") (pin "1") (pinfunction "1_1") (pintype "passive"))
      (node (ref "R11") (pin "2") (pinfunction "2_2") (pintype "passive"))
      (node (ref "Rf12") (pin "1") (pinfunction "1_1") (pintype "passive"))
      (node (ref "Rs1") (pin "2") (pinfunction "2_2") (pintype "passive"))
      (node (ref "U12") (pin "1") (pinfunction "Vin_1") (pintype "power_in"))
      (node (ref "U12") (pin "2") (pinfunction "Vinsns_2") (pintype "input"))
    )
    (net (code "25") (name "Net-(U12-Vref)") (class "Default")
      (node (ref "C18") (pin "1") (pinfunction "1_1") (pintype "passive"))
      (node (ref "U12") (pin "12") (pinfunction "Vref_12") (pintype "output"))
    )
    (net (code "26") (name "Net-(U21-Ictrl_minus)") (class "Default")
      (node (ref "Cf21") (pin "2") (pinfunction "2_2") (pintype "passive"))
      (node (ref "Rf22") (pin "2") (pinfunction "2_2") (pintype "passive"))
      (node (ref "U21") (pin "6") (pinfunction "Ictrl_minus_6") (pintype "input"))
    )
    (net (code "27") (name "Net-(U21-Ictrl_plus)") (class "Default")
      (node (ref "Cf21") (pin "1") (pinfunction "1_1") (pintype "passive"))
      (node (ref "Rf21") (pin "2") (pinfunction "2_2") (pintype "passive"))
      (node (ref "U21") (pin "7") (pinfunction "Ictrl_plus_7") (pintype "input"))
    )
    (net (code "28") (name "Net-(U21-Lx)") (class "Default")
      (node (ref "Lx2") (pin "2") (pinfunction "2_2") (pintype "passive"))
      (node (ref "U21") (pin "3") (pinfunction "Lx_3") (pintype "input"))
    )
    (net (code "29") (name "Net-(U21-MPP-SET)") (class "Default")
      (node (ref "C24") (pin "1") (pinfunction "1_1") (pintype "passive"))
      (node (ref "R23") (pin "1") (pinfunction "1_1") (pintype "passive"))
      (node (ref "U21") (pin "1") (pinfunction "MPP-SET_1") (pintype "input"))
      (node (ref "U21") (pin "8") (pinfunction "Xshut_8") (pintype "input"))
    )
    (net (code "30") (name "Net-(U21-Vctrl)") (class "Default")
      (node (ref "C22") (pin "1") (pinfunction "1_1") (pintype "passive"))
      (node (ref "R21") (pin "1") (pinfunction "1_1") (pintype "passive"))
      (node (ref "R22") (pin "2") (pinfunction "2_2") (pintype "passive"))
      (node (ref "U21") (pin "5") (pinfunction "Vctrl_5") (pintype "input"))
    )
    (net (code "31") (name "Net-(U21-Vout)") (class "Default")
      (node (ref "Cout2") (pin "2") (pinfunction "2_2") (pintype "passive"))
      (node (ref "Dout2") (pin "1") (pinfunction "1_1") (pintype "passive"))
      (node (ref "Rf21") (pin "1") (pinfunction "1_1") (pintype "passive"))
      (node (ref "Rs2") (pin "1") (pinfunction "1_1") (pintype "passive"))
      (node (ref "U21") (pin "4") (pinfunction "Vout_4") (pintype "output"))
    )
    (net (code "32") (name "Net-(U22-Iend)") (class "Default")
      (node (ref "R26") (pin "1") (pinfunction "1_1") (pintype "passive"))
      (node (ref "U22") (pin "13") (pinfunction "Iend_13") (pintype "bidirectional"))
    )
    (net (code "33") (name "Net-(U22-Ipre)") (class "Default")
      (node (ref "R24") (pin "1") (pinfunction "1_1") (pintype "passive"))
      (node (ref "U22") (pin "16") (pinfunction "Ipre_16") (pintype "input"))
    )
    (net (code "34") (name "Net-(U22-Iprg)") (class "Default")
      (node (ref "R25") (pin "1") (pinfunction "1_1") (pintype "passive"))
      (node (ref "U22") (pin "15") (pinfunction "Iprg_15") (pintype "input"))
    )
    (net (code "35") (name "Net-(U22-Tprg)") (class "Default")
      (node (ref "C26") (pin "2") (pinfunction "2_2") (pintype "passive"))
      (node (ref "U22") (pin "5") (pinfunction "Tprg_5") (pintype "input"))
    )
    (net (code "36") (name "Net-(U22-Vin)") (class "Default")
      (node (ref "C25") (pin "1") (pinfunction "1_1") (pintype "passive"))
      (node (ref "R21") (pin "2") (pinfunction "2_2") (pintype "passive"))
      (node (ref "Rf22") (pin "1") (pinfunction "1_1") (pintype "passive"))
      (node (ref "Rs2") (pin "2") (pinfunction "2_2") (pintype "passive"))
      (node (ref "U22") (pin "1") (pinfunction "Vin_1") (pintype "power_in"))
      (node (ref "U22") (pin "2") (pinfunction "Vinsns_2") (pintype "input"))
    )
    (net (code "37") (name "Net-(U22-Vref)") (class "Default")
      (node (ref "C28") (pin "1") (pinfunction "1_1") (pintype "passive"))
      (node (ref "U22") (pin "12") (pinfunction "Vref_12") (pintype "output"))
    )
    (net (code "38") (name "Net-(U31-Ictrl_minus)") (class "Default")
      (node (ref "Cf31") (pin "2") (pinfunction "2_2") (pintype "passive"))
      (node (ref "Rf32") (pin "2") (pinfunction "2_2") (pintype "passive"))
      (node (ref "U31") (pin "6") (pinfunction "Ictrl_minus_6") (pintype "input"))
    )
    (net (code "39") (name "Net-(U31-Ictrl_plus)") (class "Default")
      (node (ref "Cf31") (pin "1") (pinfunction "1_1") (pintype "passive"))
      (node (ref "Rf31") (pin "2") (pinfunction "2_2") (pintype "passive"))
      (node (ref "U31") (pin "7") (pinfunction "Ictrl_plus_7") (pintype "input"))
    )
    (net (code "40") (name "Net-(U31-Lx)") (class "Default")
      (node (ref "Lx3") (pin "2") (pinfunction "2_2") (pintype "passive"))
      (node (ref "U31") (pin "3") (pinfunction "Lx_3") (pintype "input"))
    )
    (net (code "41") (name "Net-(U31-MPP-SET)") (class "Default")
      (node (ref "C34") (pin "1") (pinfunction "1_1") (pintype "passive"))
      (node (ref "R33") (pin "1") (pinfunction "1_1") (pintype "passive"))
      (node (ref "U31") (pin "1") (pinfunction "MPP-SET_1") (pintype "input"))
      (node (ref "U31") (pin "8") (pinfunction "Xshut_8") (pintype "input"))
    )
    (net (code "42") (name "Net-(U31-Vctrl)") (class "Default")
      (node (ref "C32") (pin "1") (pinfunction "1_1") (pintype "passive"))
      (node (ref "R31") (pin "1") (pinfunction "1_1") (pintype "passive"))
      (node (ref "R32") (pin "2") (pinfunction "2_2") (pintype "passive"))
      (node (ref "U31") (pin "5") (pinfunction "Vctrl_5") (pintype "input"))
    )
    (net (code "43") (name "Net-(U31-Vout)") (class "Default")
      (node (ref "Cout3") (pin "2") (pinfunction "2_2") (pintype "passive"))
      (node (ref "Dout3") (pin "1") (pinfunction "1_1") (pintype "passive"))
      (node (ref "Rf31") (pin "1") (pinfunction "1_1") (pintype "passive"))
      (node (ref "Rs3") (pin "1") (pinfunction "1_1") (pintype "passive"))
      (node (ref "U31") (pin "4") (pinfunction "Vout_4") (pintype "output"))
    )
    (net (code "44") (name "Net-(U32-Iend)") (class "Default")
      (node (ref "R36") (pin "1") (pinfunction "1_1") (pintype "passive"))
      (node (ref "U32") (pin "13") (pinfunction "Iend_13") (pintype "bidirectional"))
    )
    (net (code "45") (name "Net-(U32-Ipre)") (class "Default")
      (node (ref "R34") (pin "1") (pinfunction "1_1") (pintype "passive"))
      (node (ref "U32") (pin "16") (pinfunction "Ipre_16") (pintype "input"))
    )
    (net (code "46") (name "Net-(U32-Iprg)") (class "Default")
      (node (ref "R35") (pin "1") (pinfunction "1_1") (pintype "passive"))
      (node (ref "U32") (pin "15") (pinfunction "Iprg_15") (pintype "input"))
    )
    (net (code "47") (name "Net-(U32-Tprg)") (class "Default")
      (node (ref "C36") (pin "2") (pinfunction "2_2") (pintype "passive"))
      (node (ref "U32") (pin "5") (pinfunction "Tprg_5") (pintype "input"))
    )
    (net (code "48") (name "Net-(U32-Vin)") (class "Default")
      (node (ref "C35") (pin "1") (pinfunction "1_1") (pintype "passive"))
      (node (ref "R31") (pin "2") (pinfunction "2_2") (pintype "passive"))
      (node (ref "Rf32") (pin "1") (pinfunction "1_1") (pintype "passive"))
      (node (ref "Rs3") (pin "2") (pinfunction "2_2") (pintype "passive"))
      (node (ref "U32") (pin "1") (pinfunction "Vin_1") (pintype "power_in"))
      (node (ref "U32") (pin "2") (pinfunction "Vinsns_2") (pintype "input"))
    )
    (net (code "49") (name "Net-(U32-Vref)") (class "Default")
      (node (ref "C38") (pin "1") (pinfunction "1_1") (pintype "passive"))
      (node (ref "U32") (pin "12") (pinfunction "Vref_12") (pintype "output"))
    )
    (net (code "50") (name "Net-(U41-Ictrl_minus)") (class "Default")
      (node (ref "Cf41") (pin "2") (pinfunction "2_2") (pintype "passive"))
      (node (ref "Rf42") (pin "2") (pinfunction "2_2") (pintype "passive"))
      (node (ref "U41") (pin "6") (pinfunction "Ictrl_minus_6") (pintype "input"))
    )
    (net (code "51") (name "Net-(U41-Ictrl_plus)") (class "Default")
      (node (ref "Cf41") (pin "1") (pinfunction "1_1") (pintype "passive"))
      (node (ref "Rf41") (pin "2") (pinfunction "2_2") (pintype "passive"))
      (node (ref "U41") (pin "7") (pinfunction "Ictrl_plus_7") (pintype "input"))
    )
    (net (code "52") (name "Net-(U41-Lx)") (class "Default")
      (node (ref "Lx4") (pin "2") (pinfunction "2_2") (pintype "passive"))
      (node (ref "U41") (pin "3") (pinfunction "Lx_3") (pintype "input"))
    )
    (net (code "53") (name "Net-(U41-MPP-SET)") (class "Default")
      (node (ref "C44") (pin "1") (pinfunction "1_1") (pintype "passive"))
      (node (ref "R43") (pin "1") (pinfunction "1_1") (pintype "passive"))
      (node (ref "U41") (pin "1") (pinfunction "MPP-SET_1") (pintype "input"))
      (node (ref "U41") (pin "8") (pinfunction "Xshut_8") (pintype "input"))
    )
    (net (code "54") (name "Net-(U41-Vctrl)") (class "Default")
      (node (ref "C42") (pin "1") (pinfunction "1_1") (pintype "passive"))
      (node (ref "R41") (pin "1") (pinfunction "1_1") (pintype "passive"))
      (node (ref "R42") (pin "2") (pinfunction "2_2") (pintype "passive"))
      (node (ref "U41") (pin "5") (pinfunction "Vctrl_5") (pintype "input"))
    )
    (net (code "55") (name "Net-(U41-Vout)") (class "Default")
      (node (ref "Cout4") (pin "2") (pinfunction "2_2") (pintype "passive"))
      (node (ref "Dout4") (pin "1") (pinfunction "1_1") (pintype "passive"))
      (node (ref "Rf41") (pin "1") (pinfunction "1_1") (pintype "passive"))
      (node (ref "Rs4") (pin "1") (pinfunction "1_1") (pintype "passive"))
      (node (ref "U41") (pin "4") (pinfunction "Vout_4") (pintype "output"))
    )
    (net (code "56") (name "Net-(U42-Iend)") (class "Default")
      (node (ref "R46") (pin "1") (pinfunction "1_1") (pintype "passive"))
      (node (ref "U42") (pin "13") (pinfunction "Iend_13") (pintype "bidirectional"))
    )
    (net (code "57") (name "Net-(U42-Ipre)") (class "Default")
      (node (ref "R44") (pin "1") (pinfunction "1_1") (pintype "passive"))
      (node (ref "U42") (pin "16") (pinfunction "Ipre_16") (pintype "input"))
    )
    (net (code "58") (name "Net-(U42-Iprg)") (class "Default")
      (node (ref "R45") (pin "1") (pinfunction "1_1") (pintype "passive"))
      (node (ref "U42") (pin "15") (pinfunction "Iprg_15") (pintype "input"))
    )
    (net (code "59") (name "Net-(U42-Tprg)") (class "Default")
      (node (ref "C46") (pin "2") (pinfunction "2_2") (pintype "passive"))
      (node (ref "U42") (pin "5") (pinfunction "Tprg_5") (pintype "input"))
    )
    (net (code "60") (name "Net-(U42-Vin)") (class "Default")
      (node (ref "C45") (pin "1") (pinfunction "1_1") (pintype "passive"))
      (node (ref "R41") (pin "2") (pinfunction "2_2") (pintype "passive"))
      (node (ref "Rf42") (pin "1") (pinfunction "1_1") (pintype "passive"))
      (node (ref "Rs4") (pin "2") (pinfunction "2_2") (pintype "passive"))
      (node (ref "U42") (pin "1") (pinfunction "Vin_1") (pintype "power_in"))
      (node (ref "U42") (pin "2") (pinfunction "Vinsns_2") (pintype "input"))
    )
    (net (code "61") (name "Net-(U42-Vref)") (class "Default")
      (node (ref "C48") (pin "1") (pinfunction "1_1") (pintype "passive"))
      (node (ref "U42") (pin "12") (pinfunction "Vref_12") (pintype "output"))
    )
    (net (code "62") (name "Net-(U51-Ictrl_minus)") (class "Default")
      (node (ref "Cf51") (pin "2") (pinfunction "2_2") (pintype "passive"))
      (node (ref "Rf52") (pin "2") (pinfunction "2_2") (pintype "passive"))
      (node (ref "U51") (pin "6") (pinfunction "Ictrl_minus_6") (pintype "input"))
    )
    (net (code "63") (name "Net-(U51-Ictrl_plus)") (class "Default")
      (node (ref "Cf51") (pin "1") (pinfunction "1_1") (pintype "passive"))
      (node (ref "Rf51") (pin "2") (pinfunction "2_2") (pintype "passive"))
      (node (ref "U51") (pin "7") (pinfunction "Ictrl_plus_7") (pintype "input"))
    )
    (net (code "64") (name "Net-(U51-Lx)") (class "Default")
      (node (ref "Lx5") (pin "2") (pinfunction "2_2") (pintype "passive"))
      (node (ref "U51") (pin "3") (pinfunction "Lx_3") (pintype "input"))
    )
    (net (code "65") (name "Net-(U51-MPP-SET)") (class "Default")
      (node (ref "C54") (pin "1") (pinfunction "1_1") (pintype "passive"))
      (node (ref "R53") (pin "1") (pinfunction "1_1") (pintype "passive"))
      (node (ref "U51") (pin "1") (pinfunction "MPP-SET_1") (pintype "input"))
      (node (ref "U51") (pin "8") (pinfunction "Xshut_8") (pintype "input"))
    )
    (net (code "66") (name "Net-(U51-Vctrl)") (class "Default")
      (node (ref "C52") (pin "1") (pinfunction "1_1") (pintype "passive"))
      (node (ref "R51") (pin "1") (pinfunction "1_1") (pintype "passive"))
      (node (ref "R52") (pin "2") (pinfunction "2_2") (pintype "passive"))
      (node (ref "U51") (pin "5") (pinfunction "Vctrl_5") (pintype "input"))
    )
    (net (code "67") (name "Net-(U51-Vout)") (class "Default")
      (node (ref "Cout5") (pin "2") (pinfunction "2_2") (pintype "passive"))
      (node (ref "Dout5") (pin "1") (pinfunction "1_1") (pintype "passive"))
      (node (ref "Rf51") (pin "1") (pinfunction "1_1") (pintype "passive"))
      (node (ref "Rs5") (pin "1") (pinfunction "1_1") (pintype "passive"))
      (node (ref "U51") (pin "4") (pinfunction "Vout_4") (pintype "output"))
    )
    (net (code "68") (name "Net-(U52-Iend)") (class "Default")
      (node (ref "R56") (pin "1") (pinfunction "1_1") (pintype "passive"))
      (node (ref "U52") (pin "13") (pinfunction "Iend_13") (pintype "bidirectional"))
    )
    (net (code "69") (name "Net-(U52-Ipre)") (class "Default")
      (node (ref "R54") (pin "1") (pinfunction "1_1") (pintype "passive"))
      (node (ref "U52") (pin "16") (pinfunction "Ipre_16") (pintype "input"))
    )
    (net (code "70") (name "Net-(U52-Iprg)") (class "Default")
      (node (ref "R55") (pin "1") (pinfunction "1_1") (pintype "passive"))
      (node (ref "U52") (pin "15") (pinfunction "Iprg_15") (pintype "input"))
    )
    (net (code "71") (name "Net-(U52-Tprg)") (class "Default")
      (node (ref "C56") (pin "2") (pinfunction "2_2") (pintype "passive"))
      (node (ref "U52") (pin "5") (pinfunction "Tprg_5") (pintype "input"))
    )
    (net (code "72") (name "Net-(U52-Vin)") (class "Default")
      (node (ref "C55") (pin "1") (pinfunction "1_1") (pintype "passive"))
      (node (ref "R51") (pin "2") (pinfunction "2_2") (pintype "passive"))
      (node (ref "Rf52") (pin "1") (pinfunction "1_1") (pintype "passive"))
      (node (ref "Rs5") (pin "2") (pinfunction "2_2") (pintype "passive"))
      (node (ref "U52") (pin "1") (pinfunction "Vin_1") (pintype "power_in"))
      (node (ref "U52") (pin "2") (pinfunction "Vinsns_2") (pintype "input"))
    )
    (net (code "73") (name "Net-(U52-Vref)") (class "Default")
      (node (ref "C58") (pin "1") (pinfunction "1_1") (pintype "passive"))
      (node (ref "U52") (pin "12") (pinfunction "Vref_12") (pintype "output"))
    )
    (net (code "74") (name "unconnected-(U11-GND-Pad2)") (class "Default")
      (node (ref "U11") (pin "2") (pinfunction "GND_2") (pintype "passive"))
    )
    (net (code "75") (name "unconnected-(U12-TH-Pad8)") (class "Default")
      (node (ref "U12") (pin "8") (pinfunction "TH_8") (pintype "input+no_connect"))
    )
    (net (code "76") (name "unconnected-(U12-Vpre-Pad14)") (class "Default")
      (node (ref "U12") (pin "14") (pinfunction "Vpre_14") (pintype "input+no_connect"))
    )
    (net (code "77") (name "unconnected-(U21-GND-Pad2)") (class "Default")
      (node (ref "U21") (pin "2") (pinfunction "GND_2") (pintype "passive"))
    )
    (net (code "78") (name "unconnected-(U22-TH-Pad8)") (class "Default")
      (node (ref "U22") (pin "8") (pinfunction "TH_8") (pintype "input+no_connect"))
    )
    (net (code "79") (name "unconnected-(U22-Vpre-Pad14)") (class "Default")
      (node (ref "U22") (pin "14") (pinfunction "Vpre_14") (pintype "input+no_connect"))
    )
    (net (code "80") (name "unconnected-(U31-GND-Pad2)") (class "Default")
      (node (ref "U31") (pin "2") (pinfunction "GND_2") (pintype "passive"))
    )
    (net (code "81") (name "unconnected-(U32-TH-Pad8)") (class "Default")
      (node (ref "U32") (pin "8") (pinfunction "TH_8") (pintype "input+no_connect"))
    )
    (net (code "82") (name "unconnected-(U32-Vpre-Pad14)") (class "Default")
      (node (ref "U32") (pin "14") (pinfunction "Vpre_14") (pintype "input+no_connect"))
    )
    (net (code "83") (name "unconnected-(U41-GND-Pad2)") (class "Default")
      (node (ref "U41") (pin "2") (pinfunction "GND_2") (pintype "passive"))
    )
    (net (code "84") (name "unconnected-(U42-ST1-Pad4)") (class "Default")
      (node (ref "U42") (pin "4") (pinfunction "ST1_4") (pintype "open_collector"))
    )
    (net (code "85") (name "unconnected-(U42-ST2-Pad3)") (class "Default")
      (node (ref "U42") (pin "3") (pinfunction "ST2_3") (pintype "open_collector"))
    )
    (net (code "86") (name "unconnected-(U42-TH-Pad8)") (class "Default")
      (node (ref "U42") (pin "8") (pinfunction "TH_8") (pintype "input+no_connect"))
    )
    (net (code "87") (name "unconnected-(U42-Vpre-Pad14)") (class "Default")
      (node (ref "U42") (pin "14") (pinfunction "Vpre_14") (pintype "input+no_connect"))
    )
    (net (code "88") (name "unconnected-(U51-GND-Pad2)") (class "Default")
      (node (ref "U51") (pin "2") (pinfunction "GND_2") (pintype "passive"))
    )
    (net (code "89") (name "unconnected-(U52-ST1-Pad4)") (class "Default")
      (node (ref "U52") (pin "4") (pinfunction "ST1_4") (pintype "open_collector"))
    )
    (net (code "90") (name "unconnected-(U52-ST2-Pad3)") (class "Default")
      (node (ref "U52") (pin "3") (pinfunction "ST2_3") (pintype "open_collector"))
    )
    (net (code "91") (name "unconnected-(U52-TH-Pad8)") (class "Default")
      (node (ref "U52") (pin "8") (pinfunction "TH_8") (pintype "input+no_connect"))
    )
    (net (code "92") (name "unconnected-(U52-Vpre-Pad14)") (class "Default")
      (node (ref "U52") (pin "14") (pinfunction "Vpre_14") (pintype "input+no_connect"))
    )
  )
)
